# hbs_pcb.net
KiCad netlist of a schematic drawn in EAGLE
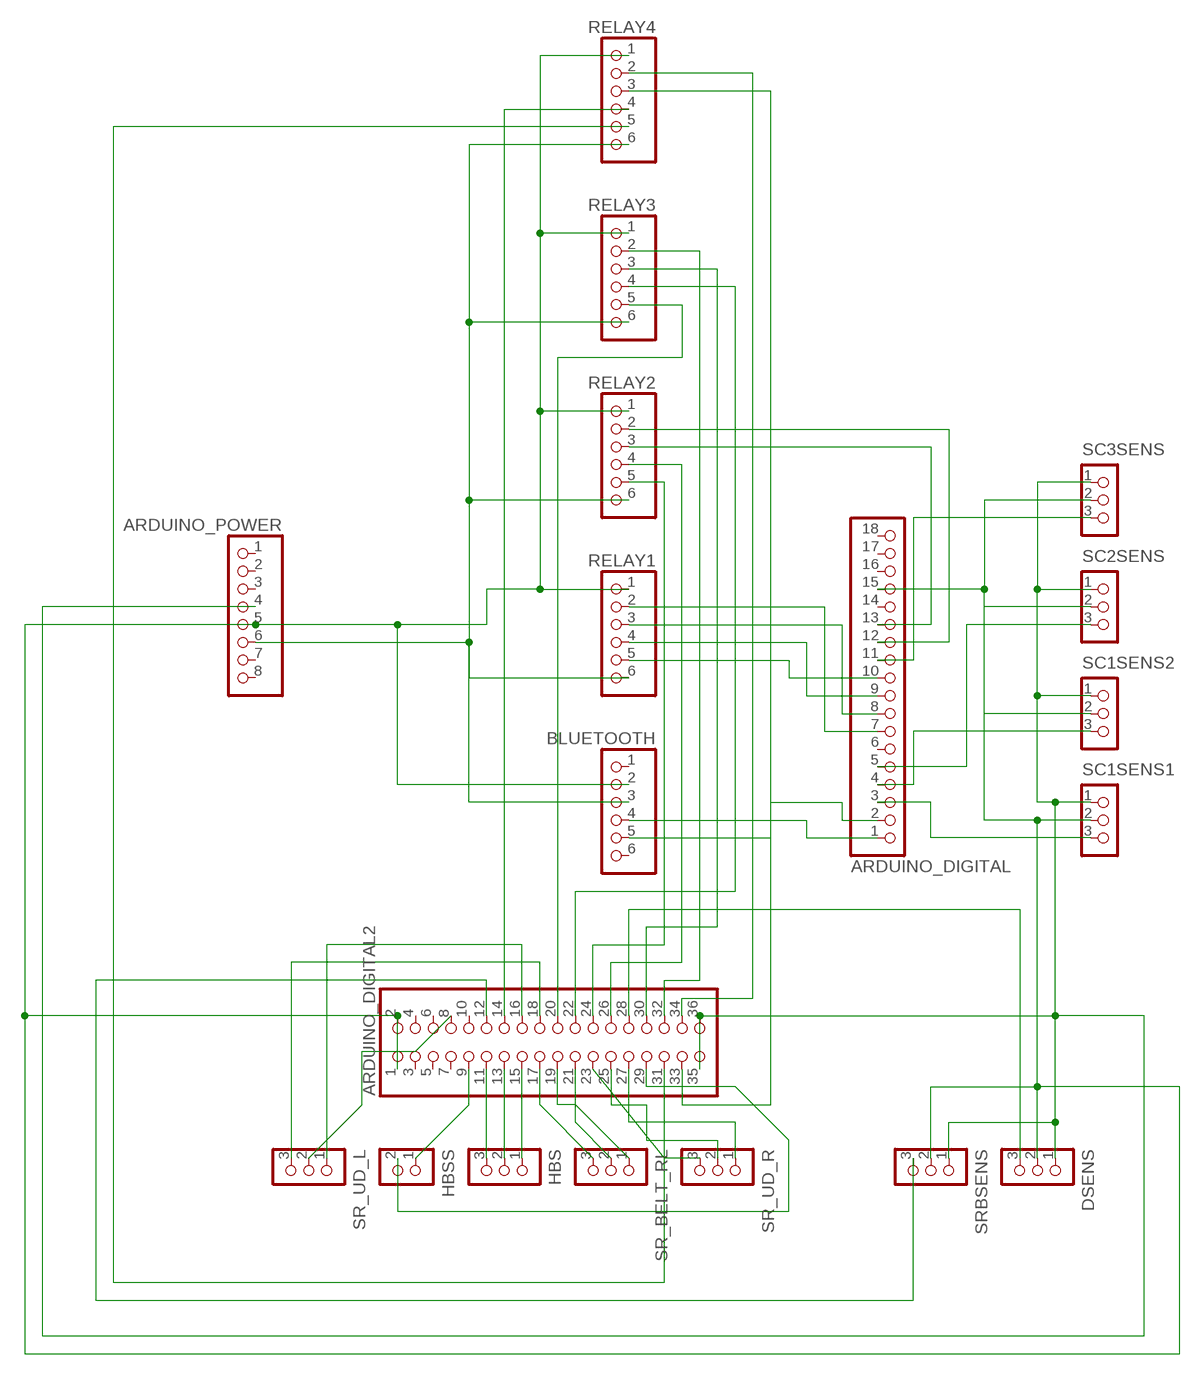
[diagram p0: schematic, sheet 1]

(export (version "E")
  (design (tool "Eeschema 10.0.6"))
  (components
    (comp (ref "ARDUINO_DIGITAL")
      (value "PINHD-1X18")
      (footprint "eagle-import:1X18")
      (libsource (lib "eagle-import") (part "PINHD-1X18"))
    )
    (comp (ref "ARDUINO_DIGITAL2")
      (value "PINHD-2X18")
      (footprint "eagle-import:2X18")
      (libsource (lib "eagle-import") (part "PINHD-2X18"))
    )
    (comp (ref "ARDUINO_POWER")
      (value "PINHD-1X8")
      (footprint "eagle-import:1X08")
      (libsource (lib "eagle-import") (part "PINHD-1X8"))
    )
    (comp (ref "BLUETOOTH")
      (value "PINHD-1X6")
      (footprint "eagle-import:1X06")
      (libsource (lib "eagle-import") (part "PINHD-1X6"))
    )
    (comp (ref "DSENS")
      (value "CON_TERMINAL_BLOCK_03-5MM")
      (footprint "eagle-import:TERMINAL_BLOCK_3P_5")
      (libsource (lib "eagle-import") (part "CON_TERMINAL_BLOCK_03-5MM"))
    )
    (comp (ref "HBS")
      (value "CON_TERMINAL_BLOCK_03-5MM")
      (footprint "eagle-import:TERMINAL_BLOCK_3P_5")
      (libsource (lib "eagle-import") (part "CON_TERMINAL_BLOCK_03-5MM"))
    )
    (comp (ref "HBSS")
      (value "CON_TERMINAL_BLOCK_02-5MM")
      (footprint "eagle-import:TERMINAL_BLOCK_2P_5")
      (libsource (lib "eagle-import") (part "CON_TERMINAL_BLOCK_02-5MM"))
    )
    (comp (ref "RELAY1")
      (value "PINHD-1X6")
      (footprint "eagle-import:1X06")
      (libsource (lib "eagle-import") (part "PINHD-1X6"))
    )
    (comp (ref "RELAY2")
      (value "PINHD-1X6")
      (footprint "eagle-import:1X06")
      (libsource (lib "eagle-import") (part "PINHD-1X6"))
    )
    (comp (ref "RELAY3")
      (value "PINHD-1X6")
      (footprint "eagle-import:1X06")
      (libsource (lib "eagle-import") (part "PINHD-1X6"))
    )
    (comp (ref "RELAY4")
      (value "PINHD-1X6")
      (footprint "eagle-import:1X06")
      (libsource (lib "eagle-import") (part "PINHD-1X6"))
    )
    (comp (ref "SC1SENS1")
      (value "CON_TERMINAL_BLOCK_03-5MM")
      (footprint "eagle-import:TERMINAL_BLOCK_3P_5")
      (libsource (lib "eagle-import") (part "CON_TERMINAL_BLOCK_03-5MM"))
    )
    (comp (ref "SC1SENS2")
      (value "CON_TERMINAL_BLOCK_03-5MM")
      (footprint "eagle-import:TERMINAL_BLOCK_3P_5")
      (libsource (lib "eagle-import") (part "CON_TERMINAL_BLOCK_03-5MM"))
    )
    (comp (ref "SC2SENS")
      (value "CON_TERMINAL_BLOCK_03-5MM")
      (footprint "eagle-import:TERMINAL_BLOCK_3P_5")
      (libsource (lib "eagle-import") (part "CON_TERMINAL_BLOCK_03-5MM"))
    )
    (comp (ref "SC3SENS")
      (value "CON_TERMINAL_BLOCK_03-5MM")
      (footprint "eagle-import:TERMINAL_BLOCK_3P_5")
      (libsource (lib "eagle-import") (part "CON_TERMINAL_BLOCK_03-5MM"))
    )
    (comp (ref "SRBSENS")
      (value "CON_TERMINAL_BLOCK_03-5MM")
      (footprint "eagle-import:TERMINAL_BLOCK_3P_5")
      (libsource (lib "eagle-import") (part "CON_TERMINAL_BLOCK_03-5MM"))
    )
    (comp (ref "SR_BELT_RL")
      (value "CON_TERMINAL_BLOCK_03-5MM")
      (footprint "eagle-import:TERMINAL_BLOCK_3P_5")
      (libsource (lib "eagle-import") (part "CON_TERMINAL_BLOCK_03-5MM"))
    )
    (comp (ref "SR_UD_L")
      (value "CON_TERMINAL_BLOCK_03-5MM")
      (footprint "eagle-import:TERMINAL_BLOCK_3P_5")
      (libsource (lib "eagle-import") (part "CON_TERMINAL_BLOCK_03-5MM"))
    )
    (comp (ref "SR_UD_R")
      (value "CON_TERMINAL_BLOCK_03-5MM")
      (footprint "eagle-import:TERMINAL_BLOCK_3P_5")
      (libsource (lib "eagle-import") (part "CON_TERMINAL_BLOCK_03-5MM"))
    )
  )
  (nets
    (net (code "1") (name "Net-(ARDUINO_DIGITAL-Pad1)") (class "Default")
      (node (ref "ARDUINO_DIGITAL") (pin "1") (pinfunction "1_1") (pintype "passive"))
      (node (ref "BLUETOOTH") (pin "4") (pinfunction "4_4") (pintype "passive"))
    )
    (net (code "2") (name "Net-(ARDUINO_DIGITAL-Pad2)") (class "Default")
      (node (ref "ARDUINO_DIGITAL") (pin "2") (pinfunction "2_2") (pintype "passive"))
      (node (ref "BLUETOOTH") (pin "5") (pinfunction "5_5") (pintype "passive"))
    )
    (net (code "3") (name "Net-(ARDUINO_DIGITAL-Pad3)") (class "Default")
      (node (ref "ARDUINO_DIGITAL") (pin "3") (pinfunction "3_3") (pintype "passive"))
      (node (ref "SC1SENS1") (pin "3") (pinfunction "3_3") (pintype "bidirectional"))
    )
    (net (code "4") (name "Net-(ARDUINO_DIGITAL-Pad4)") (class "Default")
      (node (ref "ARDUINO_DIGITAL") (pin "4") (pinfunction "4_4") (pintype "passive"))
      (node (ref "SC1SENS2") (pin "3") (pinfunction "3_3") (pintype "bidirectional"))
    )
    (net (code "5") (name "Net-(ARDUINO_DIGITAL-Pad5)") (class "Default")
      (node (ref "ARDUINO_DIGITAL") (pin "5") (pinfunction "5_5") (pintype "passive"))
      (node (ref "SC2SENS") (pin "3") (pinfunction "3_3") (pintype "bidirectional"))
    )
    (net (code "6") (name "Net-(ARDUINO_DIGITAL-Pad7)") (class "Default")
      (node (ref "ARDUINO_DIGITAL") (pin "7") (pinfunction "7_7") (pintype "passive"))
      (node (ref "RELAY1") (pin "2") (pinfunction "2_2") (pintype "passive"))
    )
    (net (code "7") (name "Net-(ARDUINO_DIGITAL-Pad8)") (class "Default")
      (node (ref "ARDUINO_DIGITAL") (pin "8") (pinfunction "8_8") (pintype "passive"))
      (node (ref "RELAY1") (pin "3") (pinfunction "3_3") (pintype "passive"))
    )
    (net (code "8") (name "Net-(ARDUINO_DIGITAL-Pad9)") (class "Default")
      (node (ref "ARDUINO_DIGITAL") (pin "9") (pinfunction "9_9") (pintype "passive"))
      (node (ref "RELAY1") (pin "4") (pinfunction "4_4") (pintype "passive"))
    )
    (net (code "9") (name "Net-(ARDUINO_DIGITAL-Pad10)") (class "Default")
      (node (ref "ARDUINO_DIGITAL") (pin "10") (pinfunction "10_10") (pintype "passive"))
      (node (ref "RELAY1") (pin "5") (pinfunction "5_5") (pintype "passive"))
    )
    (net (code "10") (name "Net-(ARDUINO_DIGITAL-Pad11)") (class "Default")
      (node (ref "ARDUINO_DIGITAL") (pin "11") (pinfunction "11_11") (pintype "passive"))
      (node (ref "SC3SENS") (pin "3") (pinfunction "3_3") (pintype "bidirectional"))
    )
    (net (code "11") (name "Net-(ARDUINO_DIGITAL-Pad12)") (class "Default")
      (node (ref "ARDUINO_DIGITAL") (pin "12") (pinfunction "12_12") (pintype "passive"))
      (node (ref "RELAY2") (pin "2") (pinfunction "2_2") (pintype "passive"))
    )
    (net (code "12") (name "Net-(ARDUINO_DIGITAL-Pad13)") (class "Default")
      (node (ref "ARDUINO_DIGITAL") (pin "13") (pinfunction "13_13") (pintype "passive"))
      (node (ref "RELAY2") (pin "3") (pinfunction "3_3") (pintype "passive"))
    )
    (net (code "13") (name "Net-(ARDUINO_DIGITAL-Pad15)") (class "Default")
      (node (ref "ARDUINO_DIGITAL") (pin "15") (pinfunction "15_15") (pintype "passive"))
      (node (ref "ARDUINO_DIGITAL2") (pin "1") (pinfunction "1_1") (pintype "passive"))
      (node (ref "ARDUINO_DIGITAL2") (pin "2") (pinfunction "2_2") (pintype "passive"))
      (node (ref "ARDUINO_POWER") (pin "5") (pinfunction "5_5") (pintype "passive"))
      (node (ref "BLUETOOTH") (pin "2") (pinfunction "2_2") (pintype "passive"))
      (node (ref "DSENS") (pin "2") (pinfunction "2_2") (pintype "bidirectional"))
      (node (ref "RELAY1") (pin "1") (pinfunction "1_1") (pintype "passive"))
      (node (ref "RELAY2") (pin "1") (pinfunction "1_1") (pintype "passive"))
      (node (ref "RELAY3") (pin "1") (pinfunction "1_1") (pintype "passive"))
      (node (ref "RELAY4") (pin "1") (pinfunction "1_1") (pintype "passive"))
      (node (ref "SC1SENS1") (pin "2") (pinfunction "2_2") (pintype "bidirectional"))
      (node (ref "SC1SENS2") (pin "2") (pinfunction "2_2") (pintype "bidirectional"))
      (node (ref "SC2SENS") (pin "2") (pinfunction "2_2") (pintype "bidirectional"))
      (node (ref "SC3SENS") (pin "2") (pinfunction "2_2") (pintype "bidirectional"))
      (node (ref "SRBSENS") (pin "2") (pinfunction "2_2") (pintype "bidirectional"))
    )
    (net (code "14") (name "Net-(ARDUINO_DIGITAL2-Pad8)") (class "Default")
      (node (ref "ARDUINO_DIGITAL2") (pin "8") (pinfunction "8_8") (pintype "passive"))
      (node (ref "SR_UD_L") (pin "2") (pinfunction "2_2") (pintype "bidirectional"))
    )
    (net (code "15") (name "Net-(ARDUINO_DIGITAL2-Pad9)") (class "Default")
      (node (ref "ARDUINO_DIGITAL2") (pin "9") (pinfunction "9_9") (pintype "passive"))
      (node (ref "HBSS") (pin "1") (pinfunction "1_1") (pintype "passive"))
    )
    (net (code "16") (name "Net-(ARDUINO_DIGITAL2-Pad11)") (class "Default")
      (node (ref "ARDUINO_DIGITAL2") (pin "11") (pinfunction "11_11") (pintype "passive"))
      (node (ref "HBS") (pin "3") (pinfunction "3_3") (pintype "bidirectional"))
    )
    (net (code "17") (name "Net-(ARDUINO_DIGITAL2-Pad12)") (class "Default")
      (node (ref "ARDUINO_DIGITAL2") (pin "12") (pinfunction "12_12") (pintype "passive"))
      (node (ref "SRBSENS") (pin "3") (pinfunction "3_3") (pintype "bidirectional"))
    )
    (net (code "18") (name "Net-(ARDUINO_DIGITAL2-Pad13)") (class "Default")
      (node (ref "ARDUINO_DIGITAL2") (pin "13") (pinfunction "13_13") (pintype "passive"))
      (node (ref "HBS") (pin "2") (pinfunction "2_2") (pintype "bidirectional"))
    )
    (net (code "19") (name "Net-(ARDUINO_DIGITAL2-Pad14)") (class "Default")
      (node (ref "ARDUINO_DIGITAL2") (pin "14") (pinfunction "14_14") (pintype "passive"))
      (node (ref "RELAY4") (pin "4") (pinfunction "4_4") (pintype "passive"))
    )
    (net (code "20") (name "Net-(ARDUINO_DIGITAL2-Pad15)") (class "Default")
      (node (ref "ARDUINO_DIGITAL2") (pin "15") (pinfunction "15_15") (pintype "passive"))
      (node (ref "HBS") (pin "1") (pinfunction "1_1") (pintype "bidirectional"))
    )
    (net (code "21") (name "Net-(ARDUINO_DIGITAL2-Pad16)") (class "Default")
      (node (ref "ARDUINO_DIGITAL2") (pin "16") (pinfunction "16_16") (pintype "passive"))
      (node (ref "SR_UD_L") (pin "1") (pinfunction "1_1") (pintype "bidirectional"))
    )
    (net (code "22") (name "Net-(ARDUINO_DIGITAL2-Pad17)") (class "Default")
      (node (ref "ARDUINO_DIGITAL2") (pin "17") (pinfunction "17_17") (pintype "passive"))
      (node (ref "SR_BELT_RL") (pin "3") (pinfunction "3_3") (pintype "bidirectional"))
    )
    (net (code "23") (name "Net-(ARDUINO_DIGITAL2-Pad18)") (class "Default")
      (node (ref "ARDUINO_DIGITAL2") (pin "18") (pinfunction "18_18") (pintype "passive"))
      (node (ref "SR_UD_L") (pin "3") (pinfunction "3_3") (pintype "bidirectional"))
    )
    (net (code "24") (name "Net-(ARDUINO_DIGITAL2-Pad19)") (class "Default")
      (node (ref "ARDUINO_DIGITAL2") (pin "19") (pinfunction "19_19") (pintype "passive"))
      (node (ref "SR_BELT_RL") (pin "1") (pinfunction "1_1") (pintype "bidirectional"))
    )
    (net (code "25") (name "Net-(ARDUINO_DIGITAL2-Pad20)") (class "Default")
      (node (ref "ARDUINO_DIGITAL2") (pin "20") (pinfunction "20_20") (pintype "passive"))
      (node (ref "RELAY3") (pin "5") (pinfunction "5_5") (pintype "passive"))
    )
    (net (code "26") (name "Net-(ARDUINO_DIGITAL2-Pad21)") (class "Default")
      (node (ref "ARDUINO_DIGITAL2") (pin "21") (pinfunction "21_21") (pintype "passive"))
      (node (ref "SR_BELT_RL") (pin "2") (pinfunction "2_2") (pintype "bidirectional"))
    )
    (net (code "27") (name "Net-(ARDUINO_DIGITAL2-Pad22)") (class "Default")
      (node (ref "ARDUINO_DIGITAL2") (pin "22") (pinfunction "22_22") (pintype "passive"))
      (node (ref "RELAY3") (pin "4") (pinfunction "4_4") (pintype "passive"))
    )
    (net (code "28") (name "Net-(ARDUINO_DIGITAL2-Pad23)") (class "Default")
      (node (ref "ARDUINO_DIGITAL2") (pin "23") (pinfunction "23_23") (pintype "passive"))
      (node (ref "SR_UD_R") (pin "3") (pinfunction "3_3") (pintype "bidirectional"))
    )
    (net (code "29") (name "Net-(ARDUINO_DIGITAL2-Pad24)") (class "Default")
      (node (ref "ARDUINO_DIGITAL2") (pin "24") (pinfunction "24_24") (pintype "passive"))
      (node (ref "RELAY2") (pin "5") (pinfunction "5_5") (pintype "passive"))
    )
    (net (code "30") (name "Net-(ARDUINO_DIGITAL2-Pad25)") (class "Default")
      (node (ref "ARDUINO_DIGITAL2") (pin "25") (pinfunction "25_25") (pintype "passive"))
      (node (ref "SR_UD_R") (pin "2") (pinfunction "2_2") (pintype "bidirectional"))
    )
    (net (code "31") (name "Net-(ARDUINO_DIGITAL2-Pad26)") (class "Default")
      (node (ref "ARDUINO_DIGITAL2") (pin "26") (pinfunction "26_26") (pintype "passive"))
      (node (ref "RELAY2") (pin "4") (pinfunction "4_4") (pintype "passive"))
    )
    (net (code "32") (name "Net-(ARDUINO_DIGITAL2-Pad27)") (class "Default")
      (node (ref "ARDUINO_DIGITAL2") (pin "27") (pinfunction "27_27") (pintype "passive"))
      (node (ref "SR_UD_R") (pin "1") (pinfunction "1_1") (pintype "bidirectional"))
    )
    (net (code "33") (name "Net-(ARDUINO_DIGITAL2-Pad28)") (class "Default")
      (node (ref "ARDUINO_DIGITAL2") (pin "28") (pinfunction "28_28") (pintype "passive"))
      (node (ref "DSENS") (pin "3") (pinfunction "3_3") (pintype "bidirectional"))
    )
    (net (code "34") (name "Net-(ARDUINO_DIGITAL2-Pad29)") (class "Default")
      (node (ref "ARDUINO_DIGITAL2") (pin "29") (pinfunction "29_29") (pintype "passive"))
      (node (ref "HBSS") (pin "2") (pinfunction "2_2") (pintype "passive"))
    )
    (net (code "35") (name "Net-(ARDUINO_DIGITAL2-Pad30)") (class "Default")
      (node (ref "ARDUINO_DIGITAL2") (pin "30") (pinfunction "30_30") (pintype "passive"))
      (node (ref "RELAY3") (pin "3") (pinfunction "3_3") (pintype "passive"))
    )
    (net (code "36") (name "Net-(ARDUINO_DIGITAL2-Pad31)") (class "Default")
      (node (ref "ARDUINO_DIGITAL2") (pin "31") (pinfunction "31_31") (pintype "passive"))
      (node (ref "RELAY4") (pin "5") (pinfunction "5_5") (pintype "passive"))
    )
    (net (code "37") (name "Net-(ARDUINO_DIGITAL2-Pad32)") (class "Default")
      (node (ref "ARDUINO_DIGITAL2") (pin "32") (pinfunction "32_32") (pintype "passive"))
      (node (ref "RELAY3") (pin "2") (pinfunction "2_2") (pintype "passive"))
    )
    (net (code "38") (name "Net-(ARDUINO_DIGITAL2-Pad33)") (class "Default")
      (node (ref "ARDUINO_DIGITAL2") (pin "33") (pinfunction "33_33") (pintype "passive"))
      (node (ref "RELAY4") (pin "3") (pinfunction "3_3") (pintype "passive"))
    )
    (net (code "39") (name "Net-(ARDUINO_DIGITAL2-Pad34)") (class "Default")
      (node (ref "ARDUINO_DIGITAL2") (pin "34") (pinfunction "34_34") (pintype "passive"))
      (node (ref "RELAY4") (pin "2") (pinfunction "2_2") (pintype "passive"))
    )
    (net (code "40") (name "Net-(ARDUINO_DIGITAL2-Pad35)") (class "Default")
      (node (ref "ARDUINO_DIGITAL2") (pin "35") (pinfunction "35_35") (pintype "passive"))
      (node (ref "ARDUINO_DIGITAL2") (pin "36") (pinfunction "36_36") (pintype "passive"))
      (node (ref "ARDUINO_POWER") (pin "4") (pinfunction "4_4") (pintype "passive"))
      (node (ref "DSENS") (pin "1") (pinfunction "1_1") (pintype "bidirectional"))
      (node (ref "SC1SENS1") (pin "1") (pinfunction "1_1") (pintype "bidirectional"))
      (node (ref "SC1SENS2") (pin "1") (pinfunction "1_1") (pintype "bidirectional"))
      (node (ref "SC2SENS") (pin "1") (pinfunction "1_1") (pintype "bidirectional"))
      (node (ref "SC3SENS") (pin "1") (pinfunction "1_1") (pintype "bidirectional"))
      (node (ref "SRBSENS") (pin "1") (pinfunction "1_1") (pintype "bidirectional"))
    )
    (net (code "41") (name "Net-(ARDUINO_POWER-Pad6)") (class "Default")
      (node (ref "ARDUINO_POWER") (pin "6") (pinfunction "6_6") (pintype "passive"))
      (node (ref "BLUETOOTH") (pin "3") (pinfunction "3_3") (pintype "passive"))
      (node (ref "RELAY1") (pin "6") (pinfunction "6_6") (pintype "passive"))
      (node (ref "RELAY2") (pin "6") (pinfunction "6_6") (pintype "passive"))
      (node (ref "RELAY3") (pin "6") (pinfunction "6_6") (pintype "passive"))
      (node (ref "RELAY4") (pin "6") (pinfunction "6_6") (pintype "passive"))
    )
    (net (code "42") (name "unconnected-(ARDUINO_DIGITAL-Pad6)") (class "Default")
      (node (ref "ARDUINO_DIGITAL") (pin "6") (pinfunction "6_6") (pintype "passive"))
    )
    (net (code "43") (name "unconnected-(ARDUINO_DIGITAL-Pad14)") (class "Default")
      (node (ref "ARDUINO_DIGITAL") (pin "14") (pinfunction "14_14") (pintype "passive"))
    )
    (net (code "44") (name "unconnected-(ARDUINO_DIGITAL-Pad16)") (class "Default")
      (node (ref "ARDUINO_DIGITAL") (pin "16") (pinfunction "16_16") (pintype "passive"))
    )
    (net (code "45") (name "unconnected-(ARDUINO_DIGITAL-Pad17)") (class "Default")
      (node (ref "ARDUINO_DIGITAL") (pin "17") (pinfunction "17_17") (pintype "passive"))
    )
    (net (code "46") (name "unconnected-(ARDUINO_DIGITAL-Pad18)") (class "Default")
      (node (ref "ARDUINO_DIGITAL") (pin "18") (pinfunction "18_18") (pintype "passive"))
    )
    (net (code "47") (name "unconnected-(ARDUINO_DIGITAL2-Pad3)") (class "Default")
      (node (ref "ARDUINO_DIGITAL2") (pin "3") (pinfunction "3_3") (pintype "passive"))
    )
    (net (code "48") (name "unconnected-(ARDUINO_DIGITAL2-Pad4)") (class "Default")
      (node (ref "ARDUINO_DIGITAL2") (pin "4") (pinfunction "4_4") (pintype "passive"))
    )
    (net (code "49") (name "unconnected-(ARDUINO_DIGITAL2-Pad5)") (class "Default")
      (node (ref "ARDUINO_DIGITAL2") (pin "5") (pinfunction "5_5") (pintype "passive"))
    )
    (net (code "50") (name "unconnected-(ARDUINO_DIGITAL2-Pad6)") (class "Default")
      (node (ref "ARDUINO_DIGITAL2") (pin "6") (pinfunction "6_6") (pintype "passive"))
    )
    (net (code "51") (name "unconnected-(ARDUINO_DIGITAL2-Pad7)") (class "Default")
      (node (ref "ARDUINO_DIGITAL2") (pin "7") (pinfunction "7_7") (pintype "passive"))
    )
    (net (code "52") (name "unconnected-(ARDUINO_DIGITAL2-Pad10)") (class "Default")
      (node (ref "ARDUINO_DIGITAL2") (pin "10") (pinfunction "10_10") (pintype "passive"))
    )
    (net (code "53") (name "unconnected-(ARDUINO_POWER-Pad1)") (class "Default")
      (node (ref "ARDUINO_POWER") (pin "1") (pinfunction "1_1") (pintype "passive"))
    )
    (net (code "54") (name "unconnected-(ARDUINO_POWER-Pad2)") (class "Default")
      (node (ref "ARDUINO_POWER") (pin "2") (pinfunction "2_2") (pintype "passive"))
    )
    (net (code "55") (name "unconnected-(ARDUINO_POWER-Pad3)") (class "Default")
      (node (ref "ARDUINO_POWER") (pin "3") (pinfunction "3_3") (pintype "passive"))
    )
    (net (code "56") (name "unconnected-(ARDUINO_POWER-Pad7)") (class "Default")
      (node (ref "ARDUINO_POWER") (pin "7") (pinfunction "7_7") (pintype "passive"))
    )
    (net (code "57") (name "unconnected-(ARDUINO_POWER-Pad8)") (class "Default")
      (node (ref "ARDUINO_POWER") (pin "8") (pinfunction "8_8") (pintype "passive"))
    )
    (net (code "58") (name "unconnected-(BLUETOOTH-Pad1)") (class "Default")
      (node (ref "BLUETOOTH") (pin "1") (pinfunction "1_1") (pintype "passive"))
    )
    (net (code "59") (name "unconnected-(BLUETOOTH-Pad6)") (class "Default")
      (node (ref "BLUETOOTH") (pin "6") (pinfunction "6_6") (pintype "passive"))
    )
  )
)
